# arduino-pro-mini_2-way-switches_v0_2_3_t.net
KiCad netlist of a schematic drawn in EAGLE
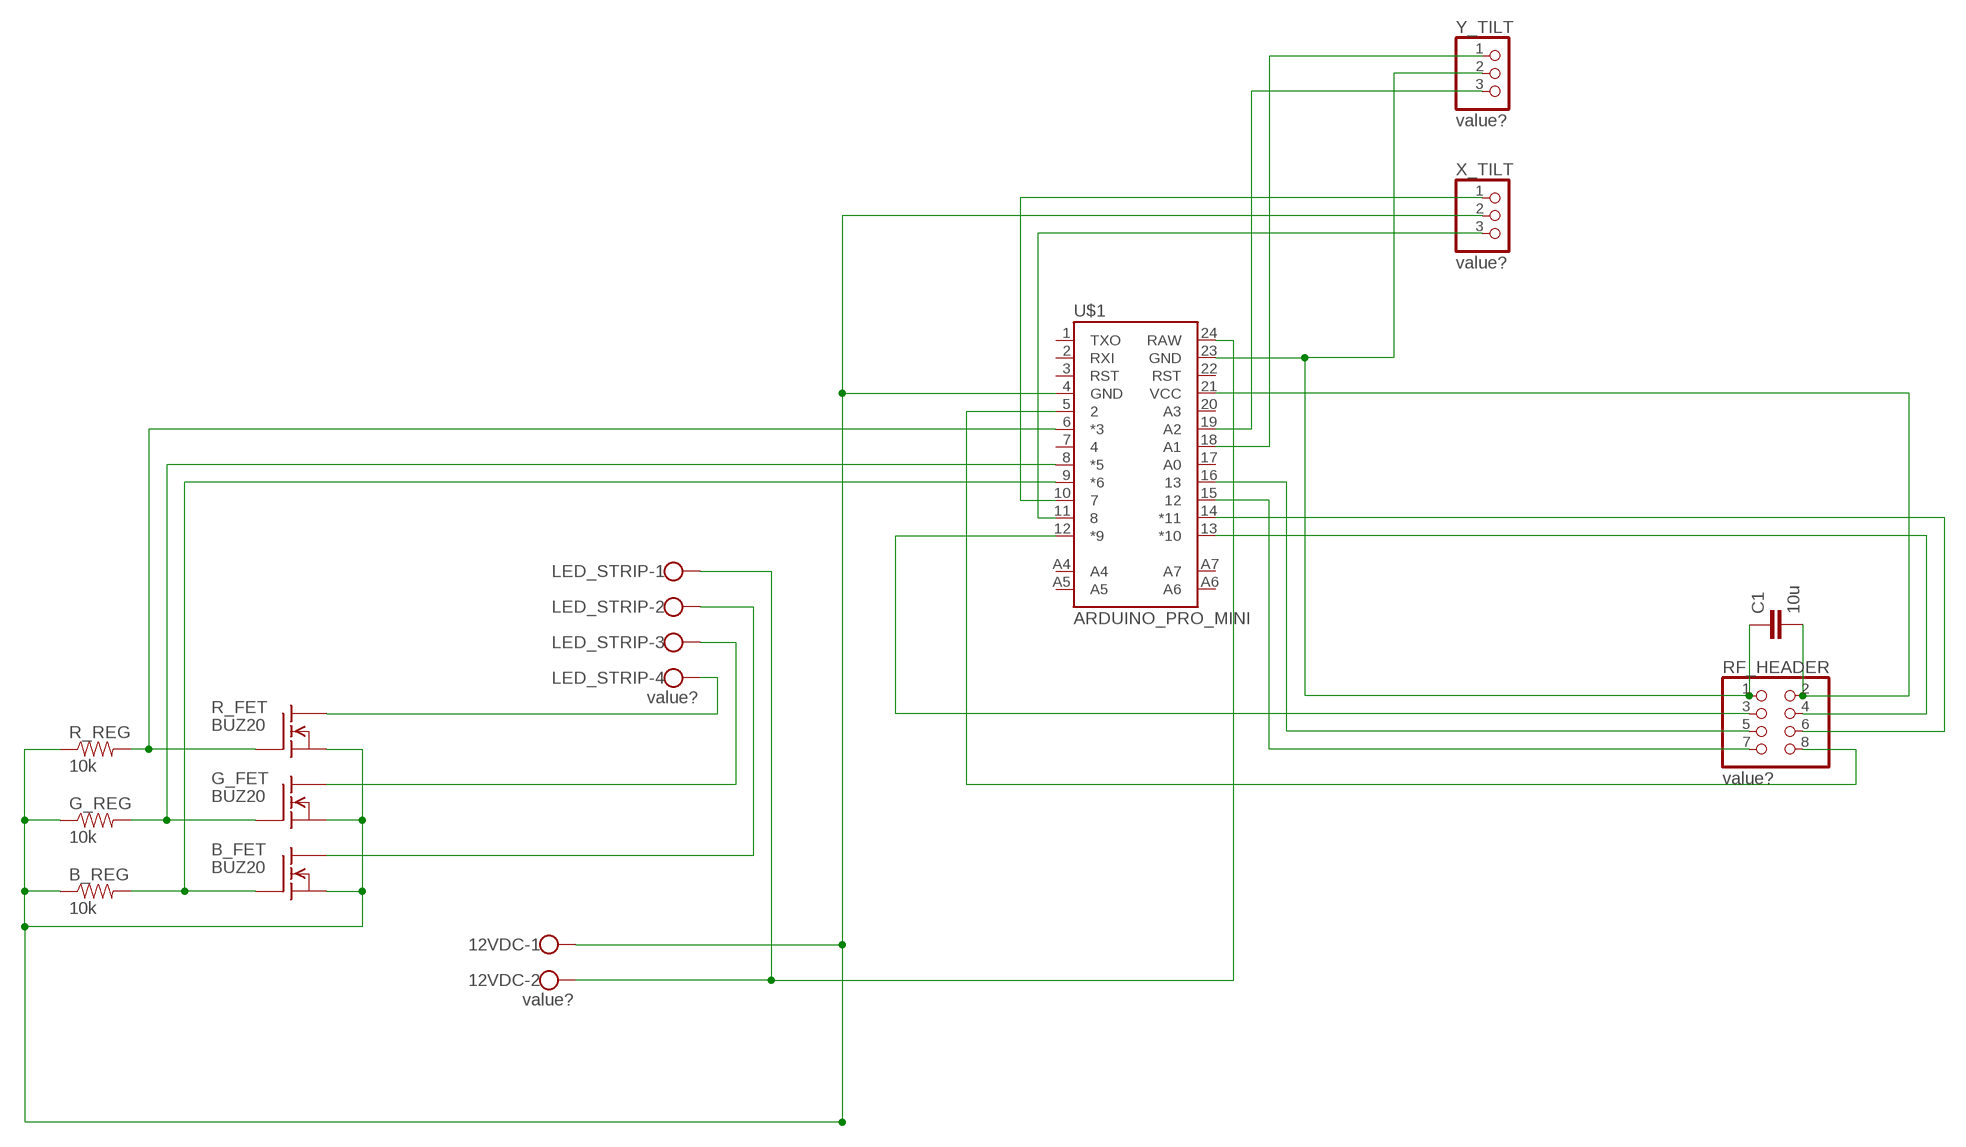
[diagram p0: schematic, sheet 1]

(export (version "E")
  (design (tool "Eeschema 10.0.6"))
  (components
    (comp (ref "12VDC")
      (value "value?")
      (footprint "eagle-import:W237-102")
      (fields (field (name "MPN") "237-102"))
      (libsource (lib "eagle-import") (part "W237-102"))
    )
    (comp (ref "B_FET")
      (value "BUZ20")
      (footprint "eagle-import:TO220")
      (libsource (lib "eagle-import") (part "BUZ20"))
    )
    (comp (ref "B_REG")
      (value "10k")
      (footprint "eagle-import:AXIAL-0.4")
      (libsource (lib "eagle-import") (part "RESISTORPTH-1/4W"))
    )
    (comp (ref "C1")
      (value "10u")
      (footprint "eagle-import:CAP-PTH-SMALL")
      (libsource (lib "eagle-import") (part "CAPPTH"))
    )
    (comp (ref "G_FET")
      (value "BUZ20")
      (footprint "eagle-import:TO220")
      (libsource (lib "eagle-import") (part "BUZ20"))
    )
    (comp (ref "G_REG")
      (value "10k")
      (footprint "eagle-import:AXIAL-0.4")
      (libsource (lib "eagle-import") (part "RESISTORPTH-1/4W"))
    )
    (comp (ref "LED_STRIP")
      (value "value?")
      (footprint "eagle-import:W237-4")
      (libsource (lib "eagle-import") (part "W237-4"))
    )
    (comp (ref "RF_HEADER")
      (value "value?")
      (footprint "eagle-import:2X04")
      (libsource (lib "eagle-import") (part "PINHD-2X4"))
    )
    (comp (ref "R_FET")
      (value "BUZ20")
      (footprint "eagle-import:TO220")
      (libsource (lib "eagle-import") (part "BUZ20"))
    )
    (comp (ref "R_REG")
      (value "10k")
      (footprint "eagle-import:AXIAL-0.4")
      (libsource (lib "eagle-import") (part "RESISTORPTH-1/4W"))
    )
    (comp (ref "U$1")
      (value "ARDUINO_PRO_MINI")
      (footprint "eagle-import:ARDUINO_PRO_MINI")
      (libsource (lib "eagle-import") (part "ARDUINO_PRO_MINI"))
    )
    (comp (ref "X_TILT")
      (value "value?")
      (footprint "eagle-import:1X03")
      (libsource (lib "eagle-import") (part "PINHD-1X3"))
    )
    (comp (ref "Y_TILT")
      (value "value?")
      (footprint "eagle-import:1X03")
      (libsource (lib "eagle-import") (part "PINHD-1X3"))
    )
  )
  (nets
    (net (code "1") (name "Net-(12VDCA-KL)") (class "Default")
      (node (ref "12VDC") (pin "1") (pinfunction "KL_1") (pintype "passive"))
      (node (ref "B_FET") (pin "3") (pinfunction "S_3") (pintype "passive"))
      (node (ref "B_REG") (pin "P$1") (pinfunction "1_P$1") (pintype "passive"))
      (node (ref "G_FET") (pin "3") (pinfunction "S_3") (pintype "passive"))
      (node (ref "G_REG") (pin "P$1") (pinfunction "1_P$1") (pintype "passive"))
      (node (ref "R_FET") (pin "3") (pinfunction "S_3") (pintype "passive"))
      (node (ref "R_REG") (pin "P$1") (pinfunction "1_P$1") (pintype "passive"))
      (node (ref "U$1") (pin "4") (pinfunction "GND_4") (pintype "bidirectional"))
      (node (ref "X_TILT") (pin "2") (pinfunction "2_2") (pintype "passive"))
    )
    (net (code "2") (name "Net-(12VDCB-KL)") (class "Default")
      (node (ref "12VDC") (pin "2") (pinfunction "KL_2") (pintype "passive"))
      (node (ref "LED_STRIP") (pin "1") (pinfunction "KL_1") (pintype "passive"))
      (node (ref "U$1") (pin "24") (pinfunction "RAW_24") (pintype "bidirectional"))
    )
    (net (code "3") (name "Net-(B_FET-D)") (class "Default")
      (node (ref "B_FET") (pin "2") (pinfunction "D_2") (pintype "passive"))
      (node (ref "LED_STRIP") (pin "2") (pinfunction "KL_2") (pintype "passive"))
    )
    (net (code "4") (name "Net-(B_FET-G)") (class "Default")
      (node (ref "B_FET") (pin "1") (pinfunction "G_1") (pintype "passive"))
      (node (ref "B_REG") (pin "P$2") (pinfunction "2_P$2") (pintype "passive"))
      (node (ref "U$1") (pin "9") (pinfunction "*6_9") (pintype "bidirectional"))
    )
    (net (code "5") (name "Net-(C1-Pad1)") (class "Default")
      (node (ref "C1") (pin "1") (pinfunction "1_1") (pintype "passive"))
      (node (ref "RF_HEADER") (pin "1") (pinfunction "1_1") (pintype "passive"))
      (node (ref "U$1") (pin "23") (pinfunction "GND_23") (pintype "bidirectional"))
      (node (ref "Y_TILT") (pin "2") (pinfunction "2_2") (pintype "passive"))
    )
    (net (code "6") (name "Net-(G_FET-D)") (class "Default")
      (node (ref "G_FET") (pin "2") (pinfunction "D_2") (pintype "passive"))
      (node (ref "LED_STRIP") (pin "3") (pinfunction "KL_3") (pintype "passive"))
    )
    (net (code "7") (name "Net-(G_FET-G)") (class "Default")
      (node (ref "G_FET") (pin "1") (pinfunction "G_1") (pintype "passive"))
      (node (ref "G_REG") (pin "P$2") (pinfunction "2_P$2") (pintype "passive"))
      (node (ref "U$1") (pin "8") (pinfunction "*5_8") (pintype "bidirectional"))
    )
    (net (code "8") (name "Net-(LED_STRIPD-KL)") (class "Default")
      (node (ref "LED_STRIP") (pin "4") (pinfunction "KL_4") (pintype "passive"))
      (node (ref "R_FET") (pin "2") (pinfunction "D_2") (pintype "passive"))
    )
    (net (code "9") (name "Net-(R_FET-G)") (class "Default")
      (node (ref "R_FET") (pin "1") (pinfunction "G_1") (pintype "passive"))
      (node (ref "R_REG") (pin "P$2") (pinfunction "2_P$2") (pintype "passive"))
      (node (ref "U$1") (pin "6") (pinfunction "*3_6") (pintype "bidirectional"))
    )
    (net (code "10") (name "Net-(U$1-*9)") (class "Default")
      (node (ref "RF_HEADER") (pin "3") (pinfunction "3_3") (pintype "passive"))
      (node (ref "U$1") (pin "12") (pinfunction "*9_12") (pintype "bidirectional"))
    )
    (net (code "11") (name "Net-(U$1-*10)") (class "Default")
      (node (ref "RF_HEADER") (pin "4") (pinfunction "4_4") (pintype "passive"))
      (node (ref "U$1") (pin "13") (pinfunction "*10_13") (pintype "bidirectional"))
    )
    (net (code "12") (name "Net-(U$1-*11)") (class "Default")
      (node (ref "RF_HEADER") (pin "6") (pinfunction "6_6") (pintype "passive"))
      (node (ref "U$1") (pin "14") (pinfunction "*11_14") (pintype "bidirectional"))
    )
    (net (code "13") (name "Net-(U$1-2)") (class "Default")
      (node (ref "RF_HEADER") (pin "8") (pinfunction "8_8") (pintype "passive"))
      (node (ref "U$1") (pin "5") (pinfunction "2_5") (pintype "bidirectional"))
    )
    (net (code "14") (name "Net-(U$1-7)") (class "Default")
      (node (ref "U$1") (pin "10") (pinfunction "7_10") (pintype "bidirectional"))
      (node (ref "X_TILT") (pin "1") (pinfunction "1_1") (pintype "passive"))
    )
    (net (code "15") (name "Net-(U$1-8)") (class "Default")
      (node (ref "U$1") (pin "11") (pinfunction "8_11") (pintype "bidirectional"))
      (node (ref "X_TILT") (pin "3") (pinfunction "3_3") (pintype "passive"))
    )
    (net (code "16") (name "Net-(U$1-12)") (class "Default")
      (node (ref "RF_HEADER") (pin "7") (pinfunction "7_7") (pintype "passive"))
      (node (ref "U$1") (pin "15") (pinfunction "12_15") (pintype "bidirectional"))
    )
    (net (code "17") (name "Net-(U$1-13)") (class "Default")
      (node (ref "RF_HEADER") (pin "5") (pinfunction "5_5") (pintype "passive"))
      (node (ref "U$1") (pin "16") (pinfunction "13_16") (pintype "bidirectional"))
    )
    (net (code "18") (name "Net-(U$1-A1)") (class "Default")
      (node (ref "U$1") (pin "18") (pinfunction "A1_18") (pintype "bidirectional"))
      (node (ref "Y_TILT") (pin "1") (pinfunction "1_1") (pintype "passive"))
    )
    (net (code "19") (name "Net-(U$1-A2)") (class "Default")
      (node (ref "U$1") (pin "19") (pinfunction "A2_19") (pintype "bidirectional"))
      (node (ref "Y_TILT") (pin "3") (pinfunction "3_3") (pintype "passive"))
    )
    (net (code "20") (name "Net-(U$1-VCC)") (class "Default")
      (node (ref "C1") (pin "2") (pinfunction "2_2") (pintype "passive"))
      (node (ref "RF_HEADER") (pin "2") (pinfunction "2_2") (pintype "passive"))
      (node (ref "U$1") (pin "21") (pinfunction "VCC_21") (pintype "bidirectional"))
    )
    (net (code "21") (name "unconnected-(U$1-4-Pad7)") (class "Default")
      (node (ref "U$1") (pin "7") (pinfunction "4_7") (pintype "bidirectional"))
    )
    (net (code "22") (name "unconnected-(U$1-A0-Pad17)") (class "Default")
      (node (ref "U$1") (pin "17") (pinfunction "A0_17") (pintype "bidirectional"))
    )
    (net (code "23") (name "unconnected-(U$1-A3-Pad20)") (class "Default")
      (node (ref "U$1") (pin "20") (pinfunction "A3_20") (pintype "bidirectional"))
    )
    (net (code "24") (name "unconnected-(U$1-PadA4)") (class "Default")
      (node (ref "U$1") (pin "A4") (pinfunction "A4_A4") (pintype "bidirectional"))
    )
    (net (code "25") (name "unconnected-(U$1-PadA5)") (class "Default")
      (node (ref "U$1") (pin "A5") (pinfunction "A5_A5") (pintype "bidirectional"))
    )
    (net (code "26") (name "unconnected-(U$1-PadA6)") (class "Default")
      (node (ref "U$1") (pin "A6") (pinfunction "A6_A6") (pintype "bidirectional"))
    )
    (net (code "27") (name "unconnected-(U$1-PadA7)") (class "Default")
      (node (ref "U$1") (pin "A7") (pinfunction "A7_A7") (pintype "bidirectional"))
    )
    (net (code "28") (name "unconnected-(U$1-RST-Pad3)") (class "Default")
      (node (ref "U$1") (pin "3") (pinfunction "RST_3") (pintype "bidirectional"))
    )
    (net (code "29") (name "unconnected-(U$1-RST-Pad22)") (class "Default")
      (node (ref "U$1") (pin "22") (pinfunction "RST_22") (pintype "bidirectional"))
    )
    (net (code "30") (name "unconnected-(U$1-RXI-Pad2)") (class "Default")
      (node (ref "U$1") (pin "2") (pinfunction "RXI_2") (pintype "bidirectional"))
    )
    (net (code "31") (name "unconnected-(U$1-TXO-Pad1)") (class "Default")
      (node (ref "U$1") (pin "1") (pinfunction "TXO_1") (pintype "bidirectional"))
    )
  )
)
